# Graphic_LCD_Backpack-v15.net
KiCad netlist of a schematic drawn in EAGLE
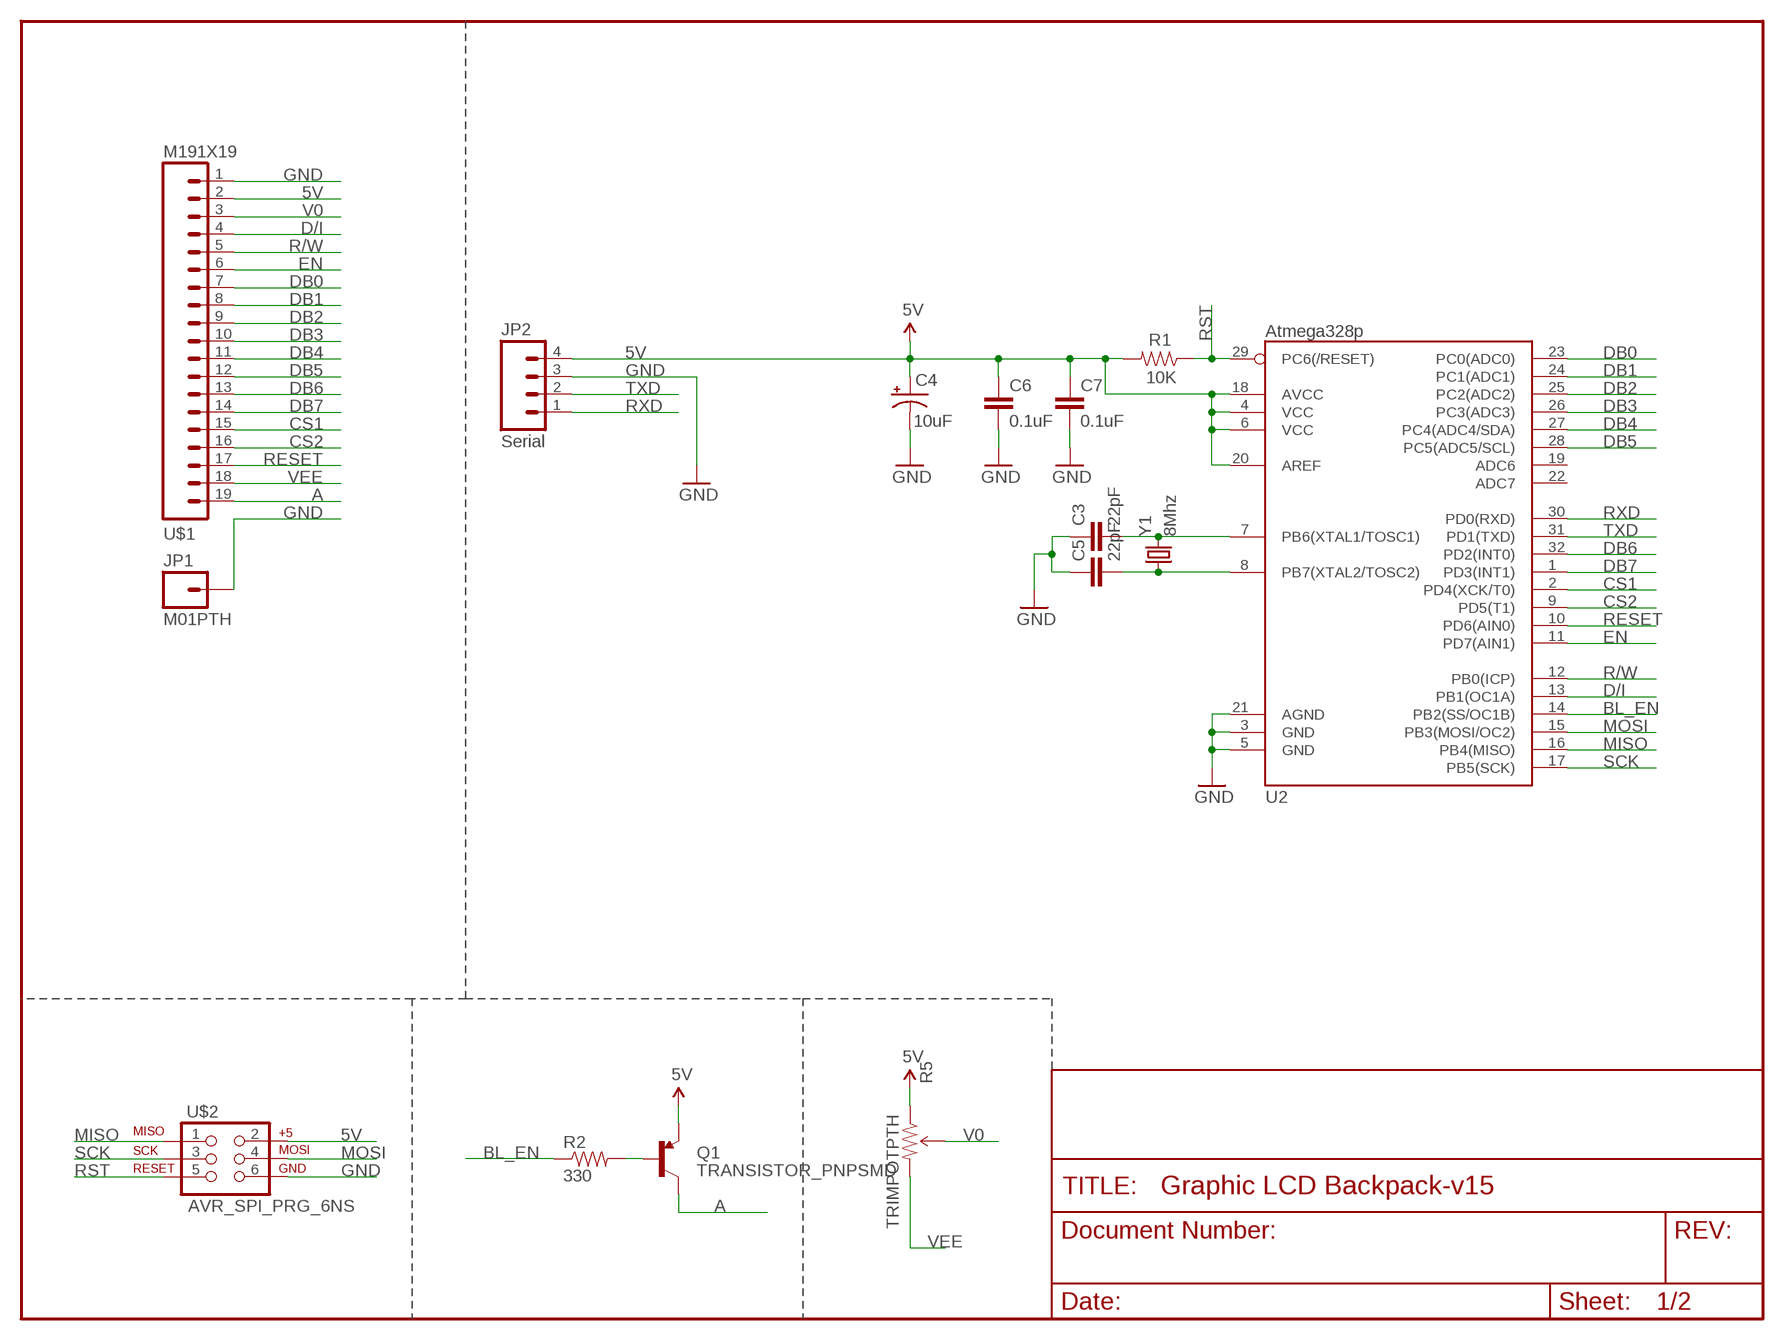
[diagram p0: schematic, sheet 1]
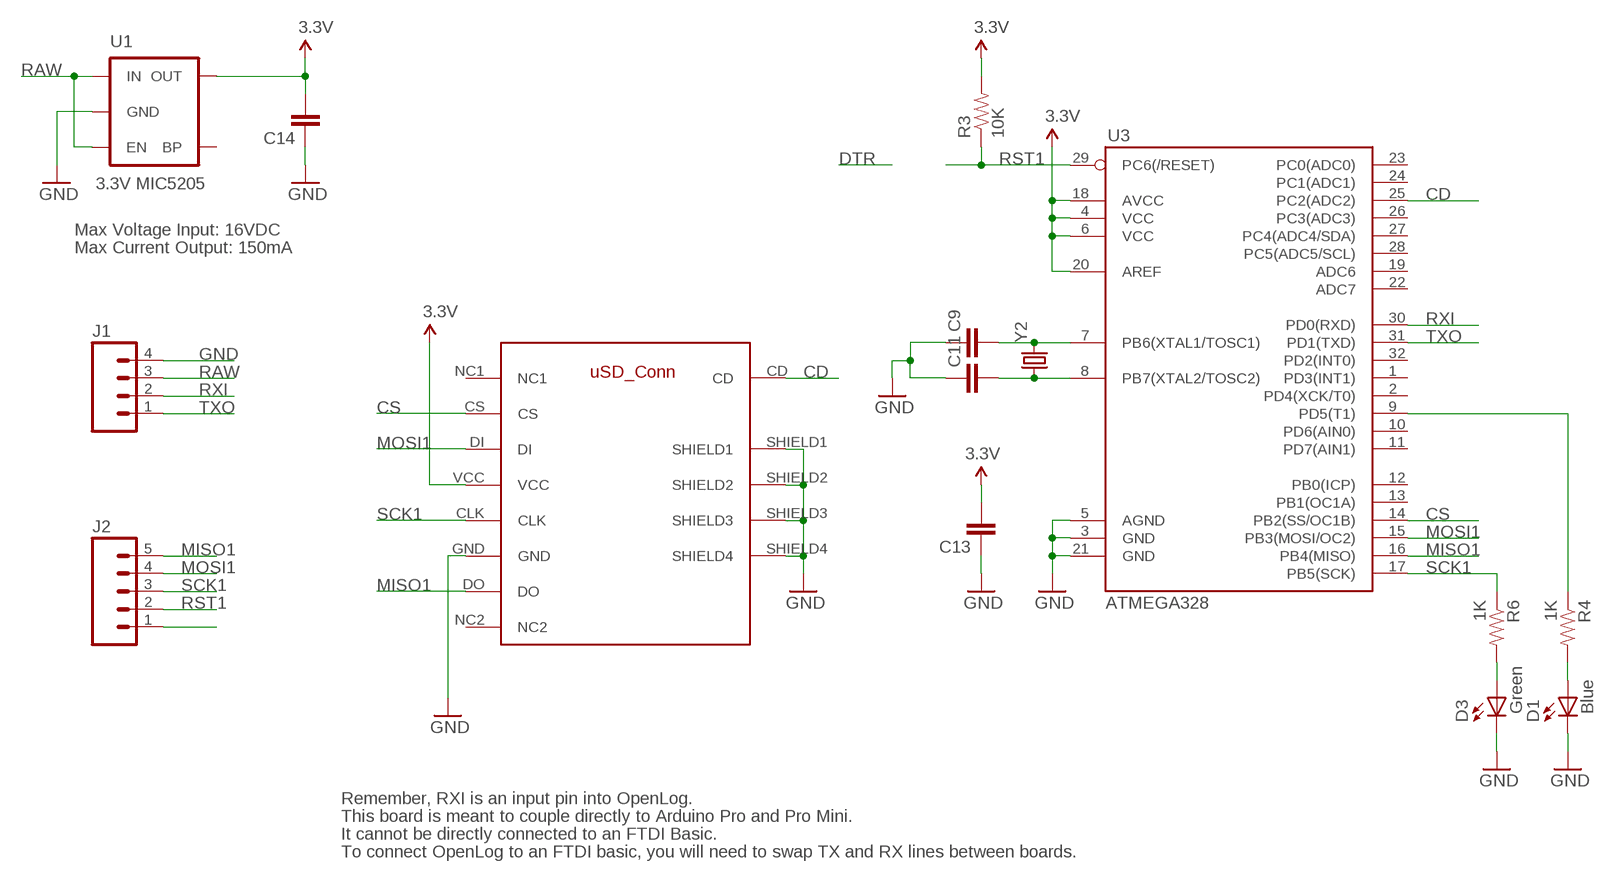
[diagram p1: schematic, sheet 2]

(export (version "E")
  (design (tool "Eeschema 10.0.6"))
  (components
    (comp (ref "C9")
      (value "CAP1206")
      (footprint "eagle-import:1206")
      (libsource (lib "eagle-import") (part "CAP1206"))
    )
    (comp (ref "C11")
      (value "CAP1206")
      (footprint "eagle-import:1206")
      (libsource (lib "eagle-import") (part "CAP1206"))
    )
    (comp (ref "C13")
      (value "CAP1206")
      (footprint "eagle-import:1206")
      (libsource (lib "eagle-import") (part "CAP1206"))
    )
    (comp (ref "C14")
      (value "CAP1206")
      (footprint "eagle-import:1206")
      (libsource (lib "eagle-import") (part "CAP1206"))
    )
    (comp (ref "D1")
      (value "Blue")
      (footprint "eagle-import:LED-1206")
      (libsource (lib "eagle-import") (part "LED1206"))
    )
    (comp (ref "D3")
      (value "Green")
      (footprint "eagle-import:LED-1206")
      (libsource (lib "eagle-import") (part "LED1206"))
    )
    (comp (ref "J1")
      (value "M04PTH")
      (footprint "eagle-import:1X04")
      (libsource (lib "eagle-import") (part "SparkFun-Connectors_M04PTH"))
    )
    (comp (ref "J2")
      (value "M05PTH")
      (footprint "eagle-import:1X05")
      (libsource (lib "eagle-import") (part "M05PTH"))
    )
    (comp (ref "R3")
      (value "10K")
      (footprint "eagle-import:0805")
      (libsource (lib "eagle-import") (part "RESISTOR"))
    )
    (comp (ref "R4")
      (value "1K")
      (footprint "eagle-import:0805")
      (libsource (lib "eagle-import") (part "RESISTOR"))
    )
    (comp (ref "R6")
      (value "1K")
      (footprint "eagle-import:0805")
      (libsource (lib "eagle-import") (part "RESISTOR"))
    )
    (comp (ref "U$3")
      (value "USD_CONN")
      (footprint "eagle-import:USD_CONN")
      (libsource (lib "eagle-import") (part "USD_CONN"))
    )
    (comp (ref "U1")
      (value "3.3V MIC5205")
      (footprint "eagle-import:SOT23-5")
      (libsource (lib "eagle-import") (part "V_REG_LDOSMD"))
    )
    (comp (ref "U3")
      (value "ATMEGA328")
      (footprint "eagle-import:TQFP32-08")
      (libsource (lib "eagle-import") (part "ATMEGA168"))
    )
    (comp (ref "Y2")
      (value "CRYSTALHC49US")
      (footprint "eagle-import:HC49US")
      (libsource (lib "eagle-import") (part "CRYSTALHC49US"))
    )
    (comp (ref "C3")
      (value "22pF")
      (footprint "eagle-import:1206")
      (libsource (lib "eagle-import") (part "CAP1206"))
    )
    (comp (ref "C4")
      (value "10uF")
      (footprint "eagle-import:EIA3216")
      (libsource (lib "eagle-import") (part "CAP_POL1206"))
    )
    (comp (ref "C5")
      (value "22pF")
      (footprint "eagle-import:1206")
      (libsource (lib "eagle-import") (part "CAP1206"))
    )
    (comp (ref "C6")
      (value "0.1uF")
      (footprint "eagle-import:1206")
      (libsource (lib "eagle-import") (part "CAP1206"))
    )
    (comp (ref "C7")
      (value "0.1uF")
      (footprint "eagle-import:1206")
      (libsource (lib "eagle-import") (part "CAP1206"))
    )
    (comp (ref "JP1")
      (value "M01PTH")
      (footprint "eagle-import:1X01")
      (libsource (lib "eagle-import") (part "M01PTH"))
    )
    (comp (ref "JP2")
      (value "Serial")
      (footprint "eagle-import:1X04")
      (libsource (lib "eagle-import") (part "M04PTH"))
    )
    (comp (ref "Q1")
      (value "TRANSISTOR_PNPSMD")
      (footprint "eagle-import:SOT23-3")
      (libsource (lib "eagle-import") (part "TRANSISTOR_PNPSMD"))
    )
    (comp (ref "R1")
      (value "10K")
      (footprint "eagle-import:0805")
      (libsource (lib "eagle-import") (part "RESISTOR"))
    )
    (comp (ref "R2")
      (value "330")
      (footprint "eagle-import:0805")
      (libsource (lib "eagle-import") (part "RESISTOR"))
    )
    (comp (ref "R5")
      (value "TRIMPOTPTH")
      (footprint "eagle-import:TRIM_POT_PTH")
      (libsource (lib "eagle-import") (part "TRIMPOTPTH"))
    )
    (comp (ref "U$1")
      (value "M191X19")
      (footprint "eagle-import:1X19")
      (libsource (lib "eagle-import") (part "M191X19"))
    )
    (comp (ref "U$2")
      (value "AVR_SPI_PRG_6NS")
      (footprint "eagle-import:2X3-NS")
      (libsource (lib "eagle-import") (part "AVR_SPI_PRG_6NS"))
    )
    (comp (ref "U2")
      (value "Atmega328p")
      (footprint "eagle-import:TQFP32-08")
      (libsource (lib "eagle-import") (part "ATMEGA328_SMT"))
    )
    (comp (ref "Y1")
      (value "8Mhz")
      (footprint "eagle-import:HC49US")
      (libsource (lib "eagle-import") (part "CRYSTALHC49US"))
    )
  )
  (nets
    (net (code "1") (name "3.3V") (class "Default")
      (node (ref "C13") (pin "2") (pinfunction "2_2") (pintype "passive"))
      (node (ref "C14") (pin "2") (pinfunction "2_2") (pintype "passive"))
      (node (ref "R3") (pin "2") (pinfunction "2_2") (pintype "passive"))
      (node (ref "U$3") (pin "VCC") (pinfunction "VCC_VCC") (pintype "bidirectional"))
      (node (ref "U1") (pin "5") (pinfunction "OUT_5") (pintype "passive"))
      (node (ref "U3") (pin "18") (pinfunction "AVCC_18") (pintype "bidirectional"))
      (node (ref "U3") (pin "20") (pinfunction "AREF_20") (pintype "bidirectional"))
      (node (ref "U3") (pin "4") (pinfunction "VCC_4") (pintype "bidirectional"))
      (node (ref "U3") (pin "6") (pinfunction "VCC_6") (pintype "bidirectional"))
    )
    (net (code "2") (name "5V") (class "Default")
      (node (ref "C4") (pin "A") (pinfunction "+_A") (pintype "passive"))
      (node (ref "C6") (pin "1") (pinfunction "1_1") (pintype "passive"))
      (node (ref "C7") (pin "1") (pinfunction "1_1") (pintype "passive"))
      (node (ref "JP2") (pin "4") (pinfunction "4_4") (pintype "passive"))
      (node (ref "Q1") (pin "2") (pinfunction "E_2") (pintype "passive"))
      (node (ref "R1") (pin "2") (pinfunction "2_2") (pintype "passive"))
      (node (ref "R5") (pin "1") (pinfunction "CCW_1") (pintype "passive"))
      (node (ref "U$1") (pin "2") (pinfunction "2_2") (pintype "passive"))
      (node (ref "U$2") (pin "2") (pinfunction "2_2") (pintype "passive"))
      (node (ref "U2") (pin "18") (pinfunction "AVCC_18") (pintype "bidirectional"))
      (node (ref "U2") (pin "20") (pinfunction "AREF_20") (pintype "bidirectional"))
      (node (ref "U2") (pin "4") (pinfunction "VCC_4") (pintype "bidirectional"))
      (node (ref "U2") (pin "6") (pinfunction "VCC_6") (pintype "bidirectional"))
    )
    (net (code "3") (name "A") (class "Default")
      (node (ref "Q1") (pin "3") (pinfunction "C_3") (pintype "passive"))
      (node (ref "U$1") (pin "19") (pinfunction "19_19") (pintype "passive"))
    )
    (net (code "4") (name "BL_EN") (class "Default")
      (node (ref "R2") (pin "1") (pinfunction "1_1") (pintype "passive"))
      (node (ref "U2") (pin "14") (pinfunction "PB2(SS/OC1B)_14") (pintype "bidirectional"))
    )
    (net (code "5") (name "CD") (class "Default")
      (node (ref "U$3") (pin "CD") (pinfunction "CD_CD") (pintype "bidirectional"))
      (node (ref "U3") (pin "25") (pinfunction "PC2(ADC2)_25") (pintype "bidirectional"))
    )
    (net (code "6") (name "CS") (class "Default")
      (node (ref "U$3") (pin "CS") (pinfunction "CS_CS") (pintype "bidirectional"))
      (node (ref "U3") (pin "14") (pinfunction "PB2(SS/OC1B)_14") (pintype "bidirectional"))
    )
    (net (code "7") (name "CS1") (class "Default")
      (node (ref "U$1") (pin "15") (pinfunction "15_15") (pintype "passive"))
      (node (ref "U2") (pin "2") (pinfunction "PD4(XCK/T0)_2") (pintype "bidirectional"))
    )
    (net (code "8") (name "CS2") (class "Default")
      (node (ref "U$1") (pin "16") (pinfunction "16_16") (pintype "passive"))
      (node (ref "U2") (pin "9") (pinfunction "PD5(T1)_9") (pintype "bidirectional"))
    )
    (net (code "9") (name "DB0") (class "Default")
      (node (ref "U$1") (pin "7") (pinfunction "7_7") (pintype "passive"))
      (node (ref "U2") (pin "23") (pinfunction "PC0(ADC0)_23") (pintype "bidirectional"))
    )
    (net (code "10") (name "DB1") (class "Default")
      (node (ref "U$1") (pin "8") (pinfunction "8_8") (pintype "passive"))
      (node (ref "U2") (pin "24") (pinfunction "PC1(ADC1)_24") (pintype "bidirectional"))
    )
    (net (code "11") (name "DB2") (class "Default")
      (node (ref "U$1") (pin "9") (pinfunction "9_9") (pintype "passive"))
      (node (ref "U2") (pin "25") (pinfunction "PC2(ADC2)_25") (pintype "bidirectional"))
    )
    (net (code "12") (name "DB3") (class "Default")
      (node (ref "U$1") (pin "10") (pinfunction "10_10") (pintype "passive"))
      (node (ref "U2") (pin "26") (pinfunction "PC3(ADC3)_26") (pintype "bidirectional"))
    )
    (net (code "13") (name "DB4") (class "Default")
      (node (ref "U$1") (pin "11") (pinfunction "11_11") (pintype "passive"))
      (node (ref "U2") (pin "27") (pinfunction "PC4(ADC4/SDA)_27") (pintype "bidirectional"))
    )
    (net (code "14") (name "DB5") (class "Default")
      (node (ref "U$1") (pin "12") (pinfunction "12_12") (pintype "passive"))
      (node (ref "U2") (pin "28") (pinfunction "PC5(ADC5/SCL)_28") (pintype "bidirectional"))
    )
    (net (code "15") (name "DB6") (class "Default")
      (node (ref "U$1") (pin "13") (pinfunction "13_13") (pintype "passive"))
      (node (ref "U2") (pin "32") (pinfunction "PD2(INT0)_32") (pintype "bidirectional"))
    )
    (net (code "16") (name "DB7") (class "Default")
      (node (ref "U$1") (pin "14") (pinfunction "14_14") (pintype "passive"))
      (node (ref "U2") (pin "1") (pinfunction "PD3(INT1)_1") (pintype "bidirectional"))
    )
    (net (code "18") (name "D{slash}I") (class "Default")
      (node (ref "U$1") (pin "4") (pinfunction "4_4") (pintype "passive"))
      (node (ref "U2") (pin "13") (pinfunction "PB1(OC1A)_13") (pintype "bidirectional"))
    )
    (net (code "19") (name "EN") (class "Default")
      (node (ref "U$1") (pin "6") (pinfunction "6_6") (pintype "passive"))
      (node (ref "U2") (pin "11") (pinfunction "PD7(AIN1)_11") (pintype "bidirectional"))
    )
    (net (code "20") (name "GND") (class "Default")
      (node (ref "C11") (pin "1") (pinfunction "1_1") (pintype "passive"))
      (node (ref "C13") (pin "1") (pinfunction "1_1") (pintype "passive"))
      (node (ref "C14") (pin "1") (pinfunction "1_1") (pintype "passive"))
      (node (ref "C3") (pin "1") (pinfunction "1_1") (pintype "passive"))
      (node (ref "C4") (pin "C") (pinfunction "-_C") (pintype "passive"))
      (node (ref "C5") (pin "1") (pinfunction "1_1") (pintype "passive"))
      (node (ref "C6") (pin "2") (pinfunction "2_2") (pintype "passive"))
      (node (ref "C7") (pin "2") (pinfunction "2_2") (pintype "passive"))
      (node (ref "C9") (pin "1") (pinfunction "1_1") (pintype "passive"))
      (node (ref "D1") (pin "C") (pinfunction "C_C") (pintype "passive"))
      (node (ref "D3") (pin "C") (pinfunction "C_C") (pintype "passive"))
      (node (ref "J1") (pin "4") (pinfunction "4_4") (pintype "passive"))
      (node (ref "J2") (pin "1") (pinfunction "1_1") (pintype "passive"))
      (node (ref "JP1") (pin "1") (pinfunction "1_1") (pintype "passive"))
      (node (ref "JP2") (pin "3") (pinfunction "3_3") (pintype "passive"))
      (node (ref "U$1") (pin "1") (pinfunction "1_1") (pintype "passive"))
      (node (ref "U$2") (pin "6") (pinfunction "6_6") (pintype "passive"))
      (node (ref "U$3") (pin "GND") (pinfunction "GND_GND") (pintype "bidirectional"))
      (node (ref "U$3") (pin "SHIELD1") (pinfunction "SHIELD1_SHIELD1") (pintype "bidirectional"))
      (node (ref "U$3") (pin "SHIELD2") (pinfunction "SHIELD2_SHIELD2") (pintype "bidirectional"))
      (node (ref "U$3") (pin "SHIELD3") (pinfunction "SHIELD3_SHIELD3") (pintype "bidirectional"))
      (node (ref "U$3") (pin "SHIELD4") (pinfunction "SHIELD4_SHIELD4") (pintype "bidirectional"))
      (node (ref "U1") (pin "2") (pinfunction "GND_2") (pintype "input"))
      (node (ref "U2") (pin "21") (pinfunction "AGND_21") (pintype "bidirectional"))
      (node (ref "U2") (pin "3") (pinfunction "GND_3") (pintype "bidirectional"))
      (node (ref "U2") (pin "5") (pinfunction "GND_5") (pintype "bidirectional"))
      (node (ref "U3") (pin "21") (pinfunction "GND_21") (pintype "bidirectional"))
      (node (ref "U3") (pin "3") (pinfunction "GND_3") (pintype "bidirectional"))
      (node (ref "U3") (pin "5") (pinfunction "AGND_5") (pintype "bidirectional"))
    )
    (net (code "21") (name "MISO") (class "Default")
      (node (ref "U$2") (pin "1") (pinfunction "1_1") (pintype "passive"))
      (node (ref "U2") (pin "16") (pinfunction "PB4(MISO)_16") (pintype "bidirectional"))
    )
    (net (code "22") (name "MISO1") (class "Default")
      (node (ref "J2") (pin "5") (pinfunction "5_5") (pintype "passive"))
      (node (ref "U$3") (pin "DO") (pinfunction "DO_DO") (pintype "bidirectional"))
      (node (ref "U3") (pin "16") (pinfunction "PB4(MISO)_16") (pintype "bidirectional"))
    )
    (net (code "23") (name "MOSI") (class "Default")
      (node (ref "U$2") (pin "4") (pinfunction "4_4") (pintype "passive"))
      (node (ref "U2") (pin "15") (pinfunction "PB3(MOSI/OC2)_15") (pintype "bidirectional"))
    )
    (net (code "24") (name "MOSI1") (class "Default")
      (node (ref "J2") (pin "4") (pinfunction "4_4") (pintype "passive"))
      (node (ref "U$3") (pin "DI") (pinfunction "DI_DI") (pintype "bidirectional"))
      (node (ref "U3") (pin "15") (pinfunction "PB3(MOSI/OC2)_15") (pintype "bidirectional"))
    )
    (net (code "25") (name "Net-(D1-PadA)") (class "Default")
      (node (ref "D1") (pin "A") (pinfunction "A_A") (pintype "passive"))
      (node (ref "R4") (pin "2") (pinfunction "2_2") (pintype "passive"))
    )
    (net (code "26") (name "Net-(D3-PadA)") (class "Default")
      (node (ref "D3") (pin "A") (pinfunction "A_A") (pintype "passive"))
      (node (ref "R6") (pin "2") (pinfunction "2_2") (pintype "passive"))
    )
    (net (code "27") (name "Net-(Q1-B)") (class "Default")
      (node (ref "Q1") (pin "1") (pinfunction "B_1") (pintype "passive"))
      (node (ref "R2") (pin "2") (pinfunction "2_2") (pintype "passive"))
    )
    (net (code "28") (name "Net-(U2-PB6(XTAL1{slash}TOSC1))") (class "Default")
      (node (ref "C3") (pin "2") (pinfunction "2_2") (pintype "passive"))
      (node (ref "U2") (pin "7") (pinfunction "PB6(XTAL1/TOSC1)_7") (pintype "bidirectional"))
      (node (ref "Y1") (pin "2") (pinfunction "2_2") (pintype "passive"))
    )
    (net (code "29") (name "Net-(U2-PB7(XTAL2{slash}TOSC2))") (class "Default")
      (node (ref "C5") (pin "2") (pinfunction "2_2") (pintype "passive"))
      (node (ref "U2") (pin "8") (pinfunction "PB7(XTAL2/TOSC2)_8") (pintype "bidirectional"))
      (node (ref "Y1") (pin "1") (pinfunction "1_1") (pintype "passive"))
    )
    (net (code "30") (name "Net-(U3-PB6(XTAL1{slash}TOSC1))") (class "Default")
      (node (ref "C9") (pin "2") (pinfunction "2_2") (pintype "passive"))
      (node (ref "U3") (pin "7") (pinfunction "PB6(XTAL1/TOSC1)_7") (pintype "bidirectional"))
      (node (ref "Y2") (pin "2") (pinfunction "2_2") (pintype "passive"))
    )
    (net (code "31") (name "Net-(U3-PB7(XTAL2{slash}TOSC2))") (class "Default")
      (node (ref "C11") (pin "2") (pinfunction "2_2") (pintype "passive"))
      (node (ref "U3") (pin "8") (pinfunction "PB7(XTAL2/TOSC2)_8") (pintype "bidirectional"))
      (node (ref "Y2") (pin "1") (pinfunction "1_1") (pintype "passive"))
    )
    (net (code "32") (name "Net-(U3-PD5(T1))") (class "Default")
      (node (ref "R4") (pin "1") (pinfunction "1_1") (pintype "passive"))
      (node (ref "U3") (pin "9") (pinfunction "PD5(T1)_9") (pintype "bidirectional"))
    )
    (net (code "33") (name "RAW") (class "Default")
      (node (ref "J1") (pin "3") (pinfunction "3_3") (pintype "passive"))
      (node (ref "U1") (pin "1") (pinfunction "IN_1") (pintype "input"))
      (node (ref "U1") (pin "3") (pinfunction "EN_3") (pintype "input"))
    )
    (net (code "34") (name "RESET") (class "Default")
      (node (ref "U$1") (pin "17") (pinfunction "17_17") (pintype "passive"))
      (node (ref "U2") (pin "10") (pinfunction "PD6(AIN0)_10") (pintype "bidirectional"))
    )
    (net (code "35") (name "RST") (class "Default")
      (node (ref "R1") (pin "1") (pinfunction "1_1") (pintype "passive"))
      (node (ref "U$2") (pin "5") (pinfunction "5_5") (pintype "passive"))
      (node (ref "U2") (pin "29") (pinfunction "PC6(/RESET)_29") (pintype "bidirectional"))
    )
    (net (code "36") (name "RST1") (class "Default")
      (node (ref "J2") (pin "2") (pinfunction "2_2") (pintype "passive"))
      (node (ref "R3") (pin "1") (pinfunction "1_1") (pintype "passive"))
      (node (ref "U3") (pin "29") (pinfunction "PC6(/RESET)_29") (pintype "bidirectional"))
    )
    (net (code "37") (name "RXD") (class "Default")
      (node (ref "JP2") (pin "1") (pinfunction "1_1") (pintype "passive"))
      (node (ref "U2") (pin "30") (pinfunction "PD0(RXD)_30") (pintype "bidirectional"))
    )
    (net (code "38") (name "RXI") (class "Default")
      (node (ref "J1") (pin "2") (pinfunction "2_2") (pintype "passive"))
      (node (ref "U3") (pin "30") (pinfunction "PD0(RXD)_30") (pintype "bidirectional"))
    )
    (net (code "39") (name "R{slash}W") (class "Default")
      (node (ref "U$1") (pin "5") (pinfunction "5_5") (pintype "passive"))
      (node (ref "U2") (pin "12") (pinfunction "PB0(ICP)_12") (pintype "bidirectional"))
    )
    (net (code "40") (name "SCK") (class "Default")
      (node (ref "U$2") (pin "3") (pinfunction "3_3") (pintype "passive"))
      (node (ref "U2") (pin "17") (pinfunction "PB5(SCK)_17") (pintype "bidirectional"))
    )
    (net (code "41") (name "SCK1") (class "Default")
      (node (ref "J2") (pin "3") (pinfunction "3_3") (pintype "passive"))
      (node (ref "R6") (pin "1") (pinfunction "1_1") (pintype "passive"))
      (node (ref "U$3") (pin "CLK") (pinfunction "CLK_CLK") (pintype "bidirectional"))
      (node (ref "U3") (pin "17") (pinfunction "PB5(SCK)_17") (pintype "bidirectional"))
    )
    (net (code "42") (name "TXD") (class "Default")
      (node (ref "JP2") (pin "2") (pinfunction "2_2") (pintype "passive"))
      (node (ref "U2") (pin "31") (pinfunction "PD1(TXD)_31") (pintype "bidirectional"))
    )
    (net (code "43") (name "TXO") (class "Default")
      (node (ref "J1") (pin "1") (pinfunction "1_1") (pintype "passive"))
      (node (ref "U3") (pin "31") (pinfunction "PD1(TXD)_31") (pintype "bidirectional"))
    )
    (net (code "44") (name "V0") (class "Default")
      (node (ref "R5") (pin "2") (pinfunction "WIPER_2") (pintype "passive"))
      (node (ref "U$1") (pin "3") (pinfunction "3_3") (pintype "passive"))
    )
    (net (code "45") (name "VEE") (class "Default")
      (node (ref "R5") (pin "3") (pinfunction "CW_3") (pintype "passive"))
      (node (ref "U$1") (pin "18") (pinfunction "18_18") (pintype "passive"))
    )
    (net (code "46") (name "unconnected-(U$3-PadNC1)") (class "Default")
      (node (ref "U$3") (pin "NC1") (pinfunction "NC1_NC1") (pintype "bidirectional"))
    )
    (net (code "47") (name "unconnected-(U$3-PadNC2)") (class "Default")
      (node (ref "U$3") (pin "NC2") (pinfunction "NC2_NC2") (pintype "bidirectional"))
    )
    (net (code "48") (name "unconnected-(U1-BP-Pad4)") (class "Default")
      (node (ref "U1") (pin "4") (pinfunction "BP_4") (pintype "input"))
    )
    (net (code "49") (name "unconnected-(U2-ADC6-Pad19)") (class "Default")
      (node (ref "U2") (pin "19") (pinfunction "ADC6_19") (pintype "bidirectional"))
    )
    (net (code "50") (name "unconnected-(U2-ADC7-Pad22)") (class "Default")
      (node (ref "U2") (pin "22") (pinfunction "ADC7_22") (pintype "bidirectional"))
    )
    (net (code "51") (name "unconnected-(U3-ADC6-Pad19)") (class "Default")
      (node (ref "U3") (pin "19") (pinfunction "ADC6_19") (pintype "bidirectional"))
    )
    (net (code "52") (name "unconnected-(U3-ADC7-Pad22)") (class "Default")
      (node (ref "U3") (pin "22") (pinfunction "ADC7_22") (pintype "bidirectional"))
    )
    (net (code "53") (name "unconnected-(U3-PB0(ICP)-Pad12)") (class "Default")
      (node (ref "U3") (pin "12") (pinfunction "PB0(ICP)_12") (pintype "bidirectional"))
    )
    (net (code "54") (name "unconnected-(U3-PB1(OC1A)-Pad13)") (class "Default")
      (node (ref "U3") (pin "13") (pinfunction "PB1(OC1A)_13") (pintype "bidirectional"))
    )
    (net (code "55") (name "unconnected-(U3-PC0(ADC0)-Pad23)") (class "Default")
      (node (ref "U3") (pin "23") (pinfunction "PC0(ADC0)_23") (pintype "bidirectional"))
    )
    (net (code "56") (name "unconnected-(U3-PC1(ADC1)-Pad24)") (class "Default")
      (node (ref "U3") (pin "24") (pinfunction "PC1(ADC1)_24") (pintype "bidirectional"))
    )
    (net (code "57") (name "unconnected-(U3-PC3(ADC3)-Pad26)") (class "Default")
      (node (ref "U3") (pin "26") (pinfunction "PC3(ADC3)_26") (pintype "bidirectional"))
    )
    (net (code "58") (name "unconnected-(U3-PC4(ADC4{slash}SDA)-Pad27)") (class "Default")
      (node (ref "U3") (pin "27") (pinfunction "PC4(ADC4/SDA)_27") (pintype "bidirectional"))
    )
    (net (code "59") (name "unconnected-(U3-PC5(ADC5{slash}SCL)-Pad28)") (class "Default")
      (node (ref "U3") (pin "28") (pinfunction "PC5(ADC5/SCL)_28") (pintype "bidirectional"))
    )
    (net (code "60") (name "unconnected-(U3-PD2(INT0)-Pad32)") (class "Default")
      (node (ref "U3") (pin "32") (pinfunction "PD2(INT0)_32") (pintype "bidirectional"))
    )
    (net (code "61") (name "unconnected-(U3-PD3(INT1)-Pad1)") (class "Default")
      (node (ref "U3") (pin "1") (pinfunction "PD3(INT1)_1") (pintype "bidirectional"))
    )
    (net (code "62") (name "unconnected-(U3-PD4(XCK{slash}T0)-Pad2)") (class "Default")
      (node (ref "U3") (pin "2") (pinfunction "PD4(XCK/T0)_2") (pintype "bidirectional"))
    )
    (net (code "63") (name "unconnected-(U3-PD6(AIN0)-Pad10)") (class "Default")
      (node (ref "U3") (pin "10") (pinfunction "PD6(AIN0)_10") (pintype "bidirectional"))
    )
    (net (code "64") (name "unconnected-(U3-PD7(AIN1)-Pad11)") (class "Default")
      (node (ref "U3") (pin "11") (pinfunction "PD7(AIN1)_11") (pintype "bidirectional"))
    )
  )
)
